# Qwiic_Hall_Effect_Sensor_TMAG5273.net
KiCad netlist of a schematic drawn in EAGLE
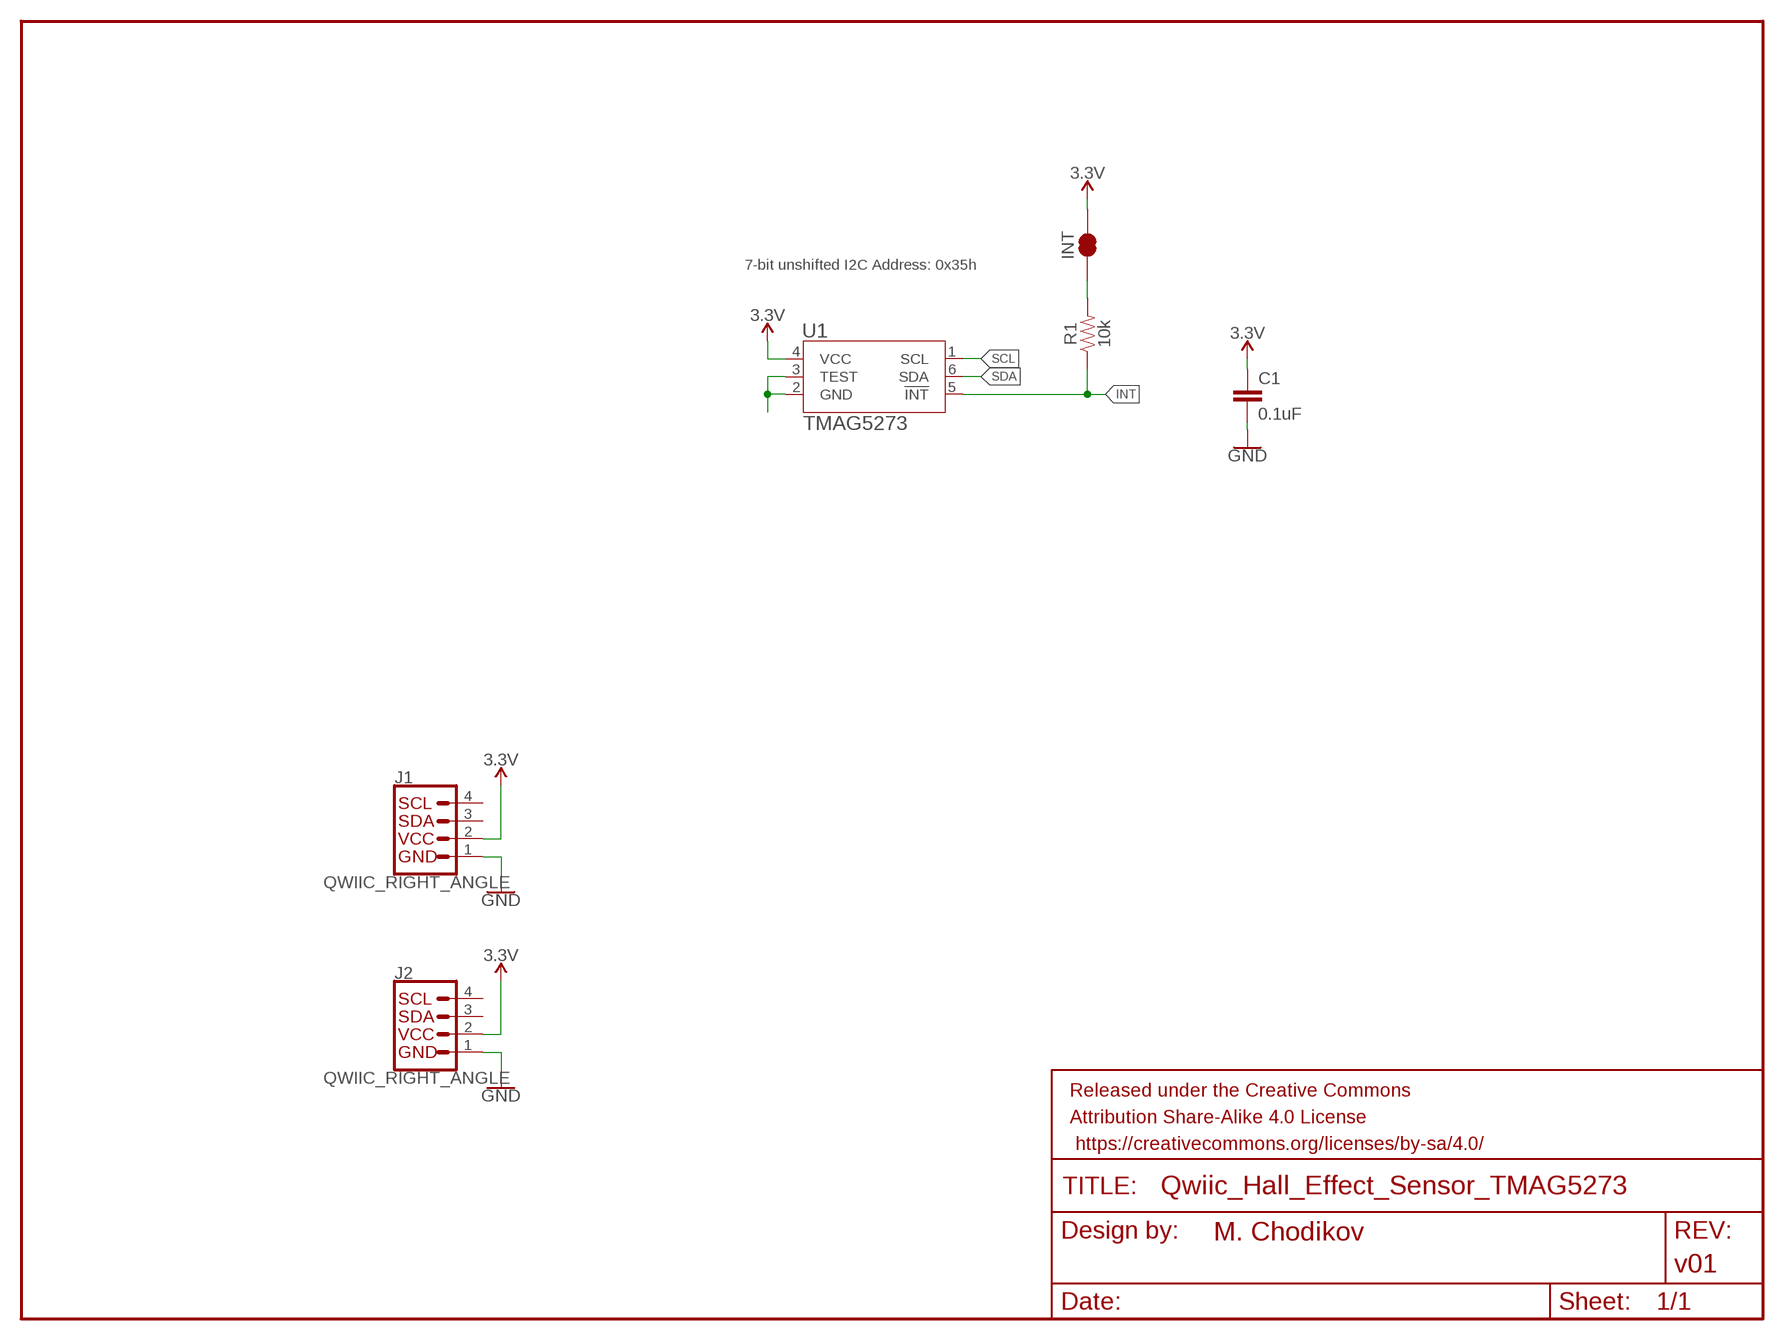
[diagram p0: schematic, sheet 1]

(export (version "E")
  (design (tool "Eeschema 10.0.6"))
  (components
    (comp (ref "C1")
      (value "0.1uF")
      (footprint "eagle-import:0402")
      (libsource (lib "eagle-import") (part "0.1UF-0402-10V-10%-X7R"))
    )
    (comp (ref "FRAME1")
      (value "FRAME-LETTER")
      (footprint "eagle-import:CREATIVE_COMMONS")
      (fields (field (name "DESIGNER") "M. Chodikov") (field (name "REV") "v01"))
      (libsource (lib "eagle-import") (part "FRAME-LETTER"))
    )
    (comp (ref "INT")
      (value "JUMPER-SMT_2_NC_TRACE_SILK")
      (footprint "eagle-import:SMT-JUMPER_2_NC_TRACE_SILK")
      (libsource (lib "eagle-import") (part "JUMPER-SMT_2_NC_TRACE_SILK"))
    )
    (comp (ref "J1")
      (value "QWIIC_RIGHT_ANGLE")
      (footprint "eagle-import:JST04_1MM_RA")
      (libsource (lib "eagle-import") (part "QWIIC_CONNECTORJS-1MM"))
    )
    (comp (ref "J2")
      (value "QWIIC_RIGHT_ANGLE")
      (footprint "eagle-import:JST04_1MM_RA")
      (libsource (lib "eagle-import") (part "QWIIC_CONNECTORJS-1MM"))
    )
    (comp (ref "R1")
      (value "10k")
      (footprint "eagle-import:0603")
      (libsource (lib "eagle-import") (part "10KOHM-0603-1/10W-1%"))
    )
    (comp (ref "U1")
      (value "TMAG5273")
      (footprint "eagle-import:SOT23-6_DBV_TEX")
      (libsource (lib "eagle-import") (part "TMAG5273A1QDBVT"))
    )
  )
  (nets
    (net (code "1") (name "3.3V") (class "Default")
      (node (ref "C1") (pin "1") (pinfunction "1_1") (pintype "passive"))
      (node (ref "INT") (pin "2") (pinfunction "2_2") (pintype "passive"))
      (node (ref "J1") (pin "2") (pinfunction "2_2") (pintype "power_in"))
      (node (ref "J2") (pin "2") (pinfunction "2_2") (pintype "power_in"))
      (node (ref "U1") (pin "4") (pinfunction "VCC_4") (pintype "power_in"))
    )
    (net (code "2") (name "GND") (class "Default")
      (node (ref "C1") (pin "2") (pinfunction "2_2") (pintype "passive"))
      (node (ref "J1") (pin "1") (pinfunction "1_1") (pintype "power_in"))
      (node (ref "J2") (pin "1") (pinfunction "1_1") (pintype "power_in"))
    )
    (net (code "3") (name "INT") (class "Default")
      (node (ref "R1") (pin "1") (pinfunction "1_1") (pintype "passive"))
      (node (ref "U1") (pin "5") (pinfunction "~{INT}_5") (pintype "bidirectional"))
    )
    (net (code "4") (name "Net-(INT-Pad1)") (class "Default")
      (node (ref "INT") (pin "1") (pinfunction "1_1") (pintype "passive"))
      (node (ref "R1") (pin "2") (pinfunction "2_2") (pintype "passive"))
    )
    (net (code "5") (name "Net-(U1-GND)") (class "Default")
      (node (ref "U1") (pin "2") (pinfunction "GND_2") (pintype "passive"))
      (node (ref "U1") (pin "3") (pinfunction "TEST_3") (pintype "input"))
    )
    (net (code "6") (name "SCL") (class "Default")
      (node (ref "U1") (pin "1") (pinfunction "SCL_1") (pintype "bidirectional"))
    )
    (net (code "7") (name "SDA") (class "Default")
      (node (ref "U1") (pin "6") (pinfunction "SDA_6") (pintype "bidirectional"))
    )
    (net (code "8") (name "unconnected-(J1-Pad3)") (class "Default")
      (node (ref "J1") (pin "3") (pinfunction "3_3") (pintype "passive"))
    )
    (net (code "9") (name "unconnected-(J1-Pad4)") (class "Default")
      (node (ref "J1") (pin "4") (pinfunction "4_4") (pintype "passive"))
    )
    (net (code "10") (name "unconnected-(J2-Pad3)") (class "Default")
      (node (ref "J2") (pin "3") (pinfunction "3_3") (pintype "passive"))
    )
    (net (code "11") (name "unconnected-(J2-Pad4)") (class "Default")
      (node (ref "J2") (pin "4") (pinfunction "4_4") (pintype "passive"))
    )
  )
)
